# coinflip.net
KiCad netlist of a schematic drawn in EAGLE
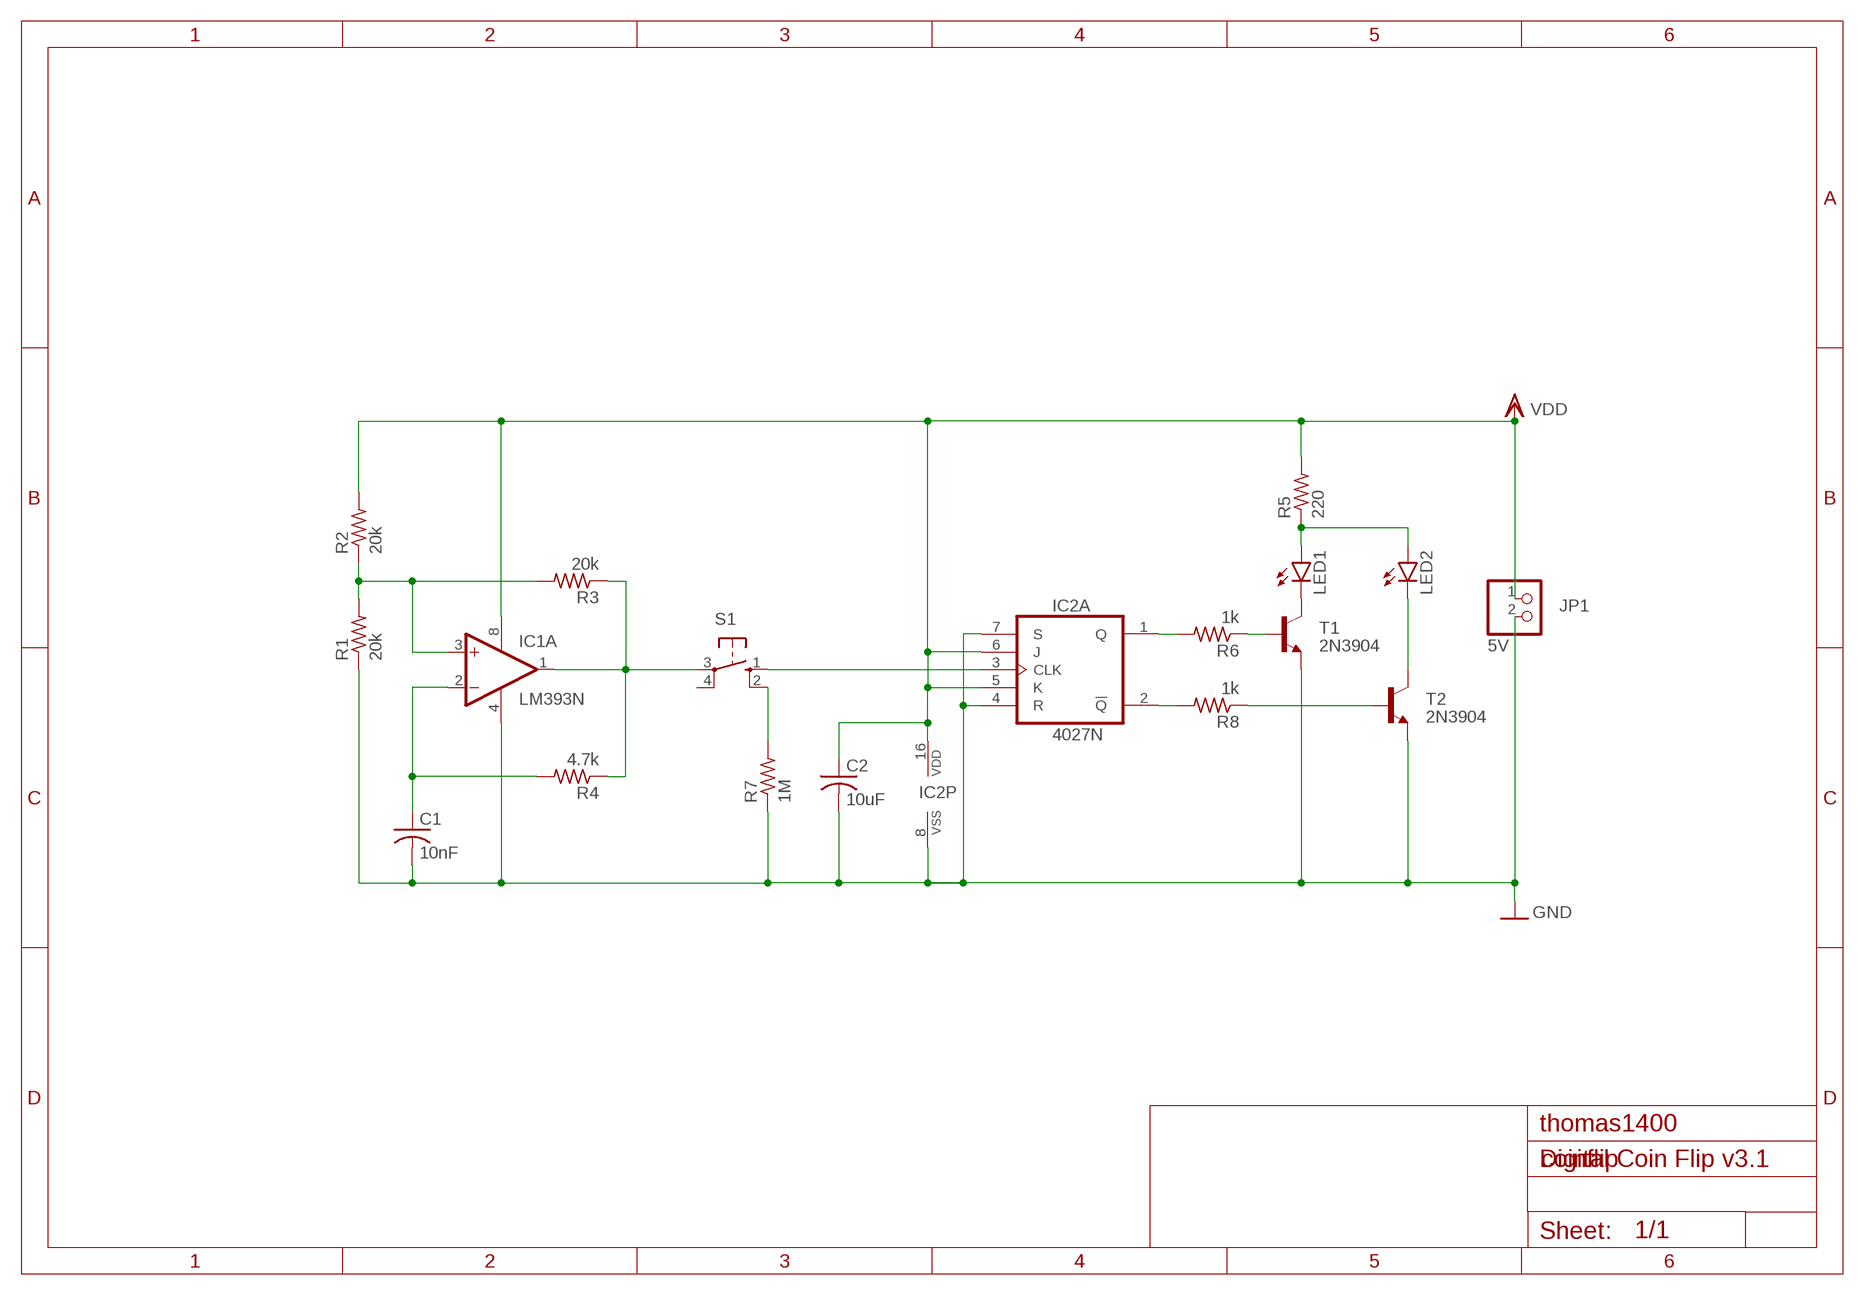
[diagram p0: schematic, sheet 1]

(export (version "E")
  (design (tool "Eeschema 10.0.6"))
  (components
    (comp (ref "C1")
      (value "10nF")
      (footprint "eagle-import:C050-024X044")
      (libsource (lib "eagle-import") (part "C-US050-024X044"))
    )
    (comp (ref "C2")
      (value "10uF")
      (footprint "eagle-import:C050-024X044")
      (libsource (lib "eagle-import") (part "C-US050-024X044"))
    )
    (comp (ref "IC1")
      (value "LM393N")
      (footprint "eagle-import:DIL08")
      (libsource (lib "eagle-import") (part "LM393N"))
    )
    (comp (ref "IC2")
      (value "4027N")
      (footprint "eagle-import:DIL16")
      (libsource (lib "eagle-import") (part "4027N"))
    )
    (comp (ref "JP1")
      (value "5V")
      (footprint "eagle-import:1X02")
      (libsource (lib "eagle-import") (part "PINHD-1X2"))
    )
    (comp (ref "LED1")
      (value "LED3MM")
      (footprint "eagle-import:LED3MM")
      (libsource (lib "eagle-import") (part "LED3MM"))
    )
    (comp (ref "LED2")
      (value "LED3MM")
      (footprint "eagle-import:LED3MM")
      (libsource (lib "eagle-import") (part "LED3MM"))
    )
    (comp (ref "R1")
      (value "20k")
      (footprint "eagle-import:0207_10")
      (libsource (lib "eagle-import") (part "R-US_0207/10"))
    )
    (comp (ref "R2")
      (value "20k")
      (footprint "eagle-import:0207_10")
      (libsource (lib "eagle-import") (part "R-US_0207/10"))
    )
    (comp (ref "R3")
      (value "20k")
      (footprint "eagle-import:0207_10")
      (libsource (lib "eagle-import") (part "R-US_0207/10"))
    )
    (comp (ref "R4")
      (value "4.7k")
      (footprint "eagle-import:0207_10")
      (libsource (lib "eagle-import") (part "R-US_0207/10"))
    )
    (comp (ref "R5")
      (value "220")
      (footprint "eagle-import:0207_10")
      (libsource (lib "eagle-import") (part "R-US_0207/10"))
    )
    (comp (ref "R6")
      (value "1k")
      (footprint "eagle-import:0207_10")
      (libsource (lib "eagle-import") (part "R-US_0207/10"))
    )
    (comp (ref "R7")
      (value "1M")
      (footprint "eagle-import:0207_10")
      (libsource (lib "eagle-import") (part "R-US_0207/10"))
    )
    (comp (ref "R8")
      (value "1k")
      (footprint "eagle-import:0207_10")
      (libsource (lib "eagle-import") (part "R-US_0207/10"))
    )
    (comp (ref "S1")
      (value "10-XX")
      (footprint "eagle-import:B3F-10XX")
      (fields (field (name "MPN") "B3F-1000"))
      (libsource (lib "eagle-import") (part "10-XX"))
    )
    (comp (ref "T1")
      (value "2N3904")
      (footprint "eagle-import:TO92")
      (libsource (lib "eagle-import") (part "2N3904"))
    )
    (comp (ref "T2")
      (value "2N3904")
      (footprint "eagle-import:TO92")
      (libsource (lib "eagle-import") (part "2N3904"))
    )
  )
  (nets
    (net (code "1") (name "GND") (class "Default")
      (node (ref "C1") (pin "2") (pinfunction "2_2") (pintype "passive"))
      (node (ref "C2") (pin "2") (pinfunction "2_2") (pintype "passive"))
      (node (ref "IC1") (pin "4") (pinfunction "V-_4") (pintype "power_in"))
      (node (ref "IC2") (pin "4") (pinfunction "R_4") (pintype "input"))
      (node (ref "IC2") (pin "7") (pinfunction "S_7") (pintype "input"))
      (node (ref "IC2") (pin "8") (pinfunction "VSS_8") (pintype "power_in"))
      (node (ref "JP1") (pin "2") (pinfunction "2_2") (pintype "passive"))
      (node (ref "R1") (pin "1") (pinfunction "1_1") (pintype "passive"))
      (node (ref "R7") (pin "1") (pinfunction "1_1") (pintype "passive"))
      (node (ref "T1") (pin "3") (pinfunction "E_3") (pintype "passive"))
      (node (ref "T2") (pin "3") (pinfunction "E_3") (pintype "passive"))
    )
    (net (code "2") (name "Net-(IC1A-+IN)") (class "Default")
      (node (ref "IC1") (pin "3") (pinfunction "+IN_3") (pintype "input"))
      (node (ref "R1") (pin "2") (pinfunction "2_2") (pintype "passive"))
      (node (ref "R2") (pin "1") (pinfunction "1_1") (pintype "passive"))
      (node (ref "R3") (pin "2") (pinfunction "2_2") (pintype "passive"))
    )
    (net (code "3") (name "Net-(IC1A--IN)") (class "Default")
      (node (ref "C1") (pin "1") (pinfunction "1_1") (pintype "passive"))
      (node (ref "IC1") (pin "2") (pinfunction "-IN_2") (pintype "input"))
      (node (ref "R4") (pin "2") (pinfunction "2_2") (pintype "passive"))
    )
    (net (code "4") (name "Net-(IC1A-OUT)") (class "Default")
      (node (ref "IC1") (pin "1") (pinfunction "OUT_1") (pintype "output"))
      (node (ref "R3") (pin "1") (pinfunction "1_1") (pintype "passive"))
      (node (ref "R4") (pin "1") (pinfunction "1_1") (pintype "passive"))
      (node (ref "S1") (pin "3") (pinfunction "P_3") (pintype "passive"))
    )
    (net (code "5") (name "Net-(IC2A-CLK)") (class "Default")
      (node (ref "IC2") (pin "3") (pinfunction "CLK_3") (pintype "input"))
      (node (ref "S1") (pin "1") (pinfunction "S_1") (pintype "passive"))
    )
    (net (code "6") (name "Net-(IC2A-Q)") (class "Default")
      (node (ref "IC2") (pin "1") (pinfunction "Q_1") (pintype "output"))
      (node (ref "R6") (pin "2") (pinfunction "2_2") (pintype "passive"))
    )
    (net (code "7") (name "Net-(IC2A-~{Q})") (class "Default")
      (node (ref "IC2") (pin "2") (pinfunction "~{Q}_2") (pintype "output"))
      (node (ref "R8") (pin "2") (pinfunction "2_2") (pintype "passive"))
    )
    (net (code "8") (name "Net-(LED1-C)") (class "Default")
      (node (ref "LED1") (pin "K") (pinfunction "C_K") (pintype "passive"))
      (node (ref "T1") (pin "1") (pinfunction "C_1") (pintype "passive"))
    )
    (net (code "9") (name "Net-(LED1-PadA)") (class "Default")
      (node (ref "LED1") (pin "A") (pinfunction "A_A") (pintype "passive"))
      (node (ref "LED2") (pin "A") (pinfunction "A_A") (pintype "passive"))
      (node (ref "R5") (pin "1") (pinfunction "1_1") (pintype "passive"))
    )
    (net (code "10") (name "Net-(LED2-C)") (class "Default")
      (node (ref "LED2") (pin "K") (pinfunction "C_K") (pintype "passive"))
      (node (ref "T2") (pin "1") (pinfunction "C_1") (pintype "passive"))
    )
    (net (code "11") (name "Net-(S1-S1)") (class "Default")
      (node (ref "R7") (pin "2") (pinfunction "2_2") (pintype "passive"))
      (node (ref "S1") (pin "2") (pinfunction "S1_2") (pintype "passive"))
    )
    (net (code "12") (name "Net-(T1-B)") (class "Default")
      (node (ref "R6") (pin "1") (pinfunction "1_1") (pintype "passive"))
      (node (ref "T1") (pin "2") (pinfunction "B_2") (pintype "passive"))
    )
    (net (code "13") (name "Net-(T2-B)") (class "Default")
      (node (ref "R8") (pin "1") (pinfunction "1_1") (pintype "passive"))
      (node (ref "T2") (pin "2") (pinfunction "B_2") (pintype "passive"))
    )
    (net (code "14") (name "VDD") (class "Default")
      (node (ref "C2") (pin "1") (pinfunction "1_1") (pintype "passive"))
      (node (ref "IC1") (pin "8") (pinfunction "V+_8") (pintype "power_in"))
      (node (ref "IC2") (pin "16") (pinfunction "VDD_16") (pintype "power_in"))
      (node (ref "IC2") (pin "5") (pinfunction "K_5") (pintype "input"))
      (node (ref "IC2") (pin "6") (pinfunction "J_6") (pintype "input"))
      (node (ref "JP1") (pin "1") (pinfunction "1_1") (pintype "passive"))
      (node (ref "R2") (pin "2") (pinfunction "2_2") (pintype "passive"))
      (node (ref "R5") (pin "2") (pinfunction "2_2") (pintype "passive"))
    )
    (net (code "15") (name "unconnected-(S1-P1-Pad4)") (class "Default")
      (node (ref "S1") (pin "4") (pinfunction "P1_4") (pintype "passive"))
    )
  )
)
